# 1wire_slave_long.net
KiCad netlist of a schematic drawn in EAGLE
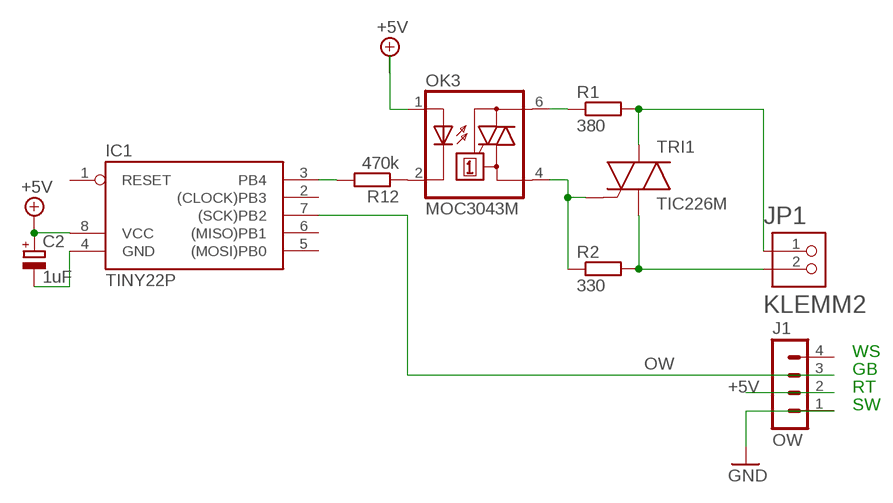
[diagram p0: schematic, sheet 1]

(export (version "E")
  (design (tool "Eeschema 10.0.6"))
  (components
    (comp (ref "C2")
      (value "1uF")
      (footprint "eagle-import:E2,5-6E")
      (libsource (lib "eagle-import") (part "CPOL-EUE2,5-6E"))
    )
    (comp (ref "IC1")
      (value "TINY22P")
      (footprint "eagle-import:DIL08")
      (libsource (lib "eagle-import") (part "TINY22P"))
    )
    (comp (ref "J1")
      (value "OW")
      (footprint "eagle-import:MA04-1")
      (libsource (lib "eagle-import") (part "MA04-1"))
    )
    (comp (ref "JP1")
      (value "KLEMM2")
      (footprint "eagle-import:KLEMM2")
      (libsource (lib "eagle-import") (part "KLEMM2"))
    )
    (comp (ref "OK3")
      (value "MOC3043M")
      (footprint "eagle-import:DIL06")
      (fields (field (name "MF") "FAIRCHILD SEMICONDUCTOR") (field (name "MPN") "MOC3043-M"))
      (libsource (lib "eagle-import") (part "MOC3043M"))
    )
    (comp (ref "R1")
      (value "380")
      (footprint "eagle-import:0204_7")
      (libsource (lib "eagle-import") (part "resistor_R-EU_0204/7"))
    )
    (comp (ref "R2")
      (value "330")
      (footprint "eagle-import:0204_7")
      (libsource (lib "eagle-import") (part "resistor_R-EU_0204/7"))
    )
    (comp (ref "R12")
      (value "470k")
      (footprint "eagle-import:0204_7")
      (libsource (lib "eagle-import") (part "R-EU_0204/7"))
    )
    (comp (ref "TRI1")
      (value "TIC226M")
      (footprint "eagle-import:TO-220A")
      (libsource (lib "eagle-import") (part "TIC226M"))
    )
  )
  (nets
    (net (code "1") (name "+5V") (class "Default")
      (node (ref "C2") (pin "+") (pinfunction "+_+") (pintype "passive"))
      (node (ref "IC1") (pin "8") (pinfunction "VCC_8") (pintype "power_in"))
      (node (ref "J1") (pin "2") (pinfunction "2_2") (pintype "passive"))
      (node (ref "OK3") (pin "1") (pinfunction "A_1") (pintype "passive"))
    )
    (net (code "2") (name "/OW") (class "Default")
      (node (ref "IC1") (pin "7") (pinfunction "(SCK)PB2_7") (pintype "bidirectional"))
      (node (ref "J1") (pin "3") (pinfunction "3_3") (pintype "passive"))
    )
    (net (code "3") (name "GND") (class "Default")
      (node (ref "C2") (pin "-") (pinfunction "-_-") (pintype "passive"))
      (node (ref "IC1") (pin "4") (pinfunction "GND_4") (pintype "power_in"))
      (node (ref "J1") (pin "1") (pinfunction "1_1") (pintype "passive"))
    )
    (net (code "4") (name "Net-(IC1-PB4)") (class "Default")
      (node (ref "IC1") (pin "3") (pinfunction "PB4_3") (pintype "bidirectional"))
      (node (ref "R12") (pin "2") (pinfunction "2_2") (pintype "passive"))
    )
    (net (code "5") (name "Net-(OK3-A1)") (class "Default")
      (node (ref "OK3") (pin "4") (pinfunction "A1_4") (pintype "passive"))
      (node (ref "R2") (pin "1") (pinfunction "1_1") (pintype "passive"))
      (node (ref "TRI1") (pin "3") (pinfunction "G_3") (pintype "passive"))
    )
    (net (code "6") (name "Net-(OK3-A2)") (class "Default")
      (node (ref "OK3") (pin "6") (pinfunction "A2_6") (pintype "passive"))
      (node (ref "R1") (pin "1") (pinfunction "1_1") (pintype "passive"))
    )
    (net (code "7") (name "Net-(OK3-C)") (class "Default")
      (node (ref "OK3") (pin "2") (pinfunction "C_2") (pintype "passive"))
      (node (ref "R12") (pin "1") (pinfunction "1_1") (pintype "passive"))
    )
    (net (code "8") (name "Net-(TRI1-A1)") (class "Default")
      (node (ref "JP1") (pin "2") (pinfunction "2_2") (pintype "passive"))
      (node (ref "R2") (pin "2") (pinfunction "2_2") (pintype "passive"))
      (node (ref "TRI1") (pin "1") (pinfunction "A1_1") (pintype "passive"))
    )
    (net (code "9") (name "Net-(TRI1-A2)") (class "Default")
      (node (ref "JP1") (pin "1") (pinfunction "1_1") (pintype "passive"))
      (node (ref "R1") (pin "2") (pinfunction "2_2") (pintype "passive"))
      (node (ref "TRI1") (pin "2") (pinfunction "A2_2") (pintype "passive"))
    )
    (net (code "10") (name "unconnected-(IC1-(CLOCK)PB3-Pad2)") (class "Default")
      (node (ref "IC1") (pin "2") (pinfunction "(CLOCK)PB3_2") (pintype "bidirectional"))
    )
    (net (code "11") (name "unconnected-(IC1-(MISO)PB1-Pad6)") (class "Default")
      (node (ref "IC1") (pin "6") (pinfunction "(MISO)PB1_6") (pintype "bidirectional"))
    )
    (net (code "12") (name "unconnected-(IC1-(MOSI)PB0-Pad5)") (class "Default")
      (node (ref "IC1") (pin "5") (pinfunction "(MOSI)PB0_5") (pintype "bidirectional"))
    )
    (net (code "13") (name "unconnected-(IC1-RESET-Pad1)") (class "Default")
      (node (ref "IC1") (pin "1") (pinfunction "RESET_1") (pintype "input"))
    )
    (net (code "14") (name "unconnected-(J1-Pad4)") (class "Default")
      (node (ref "J1") (pin "4") (pinfunction "4_4") (pintype "passive"))
    )
  )
)
